# BLDC_wireless_project.net
KiCad netlist of a schematic drawn in EasyEDA Pro
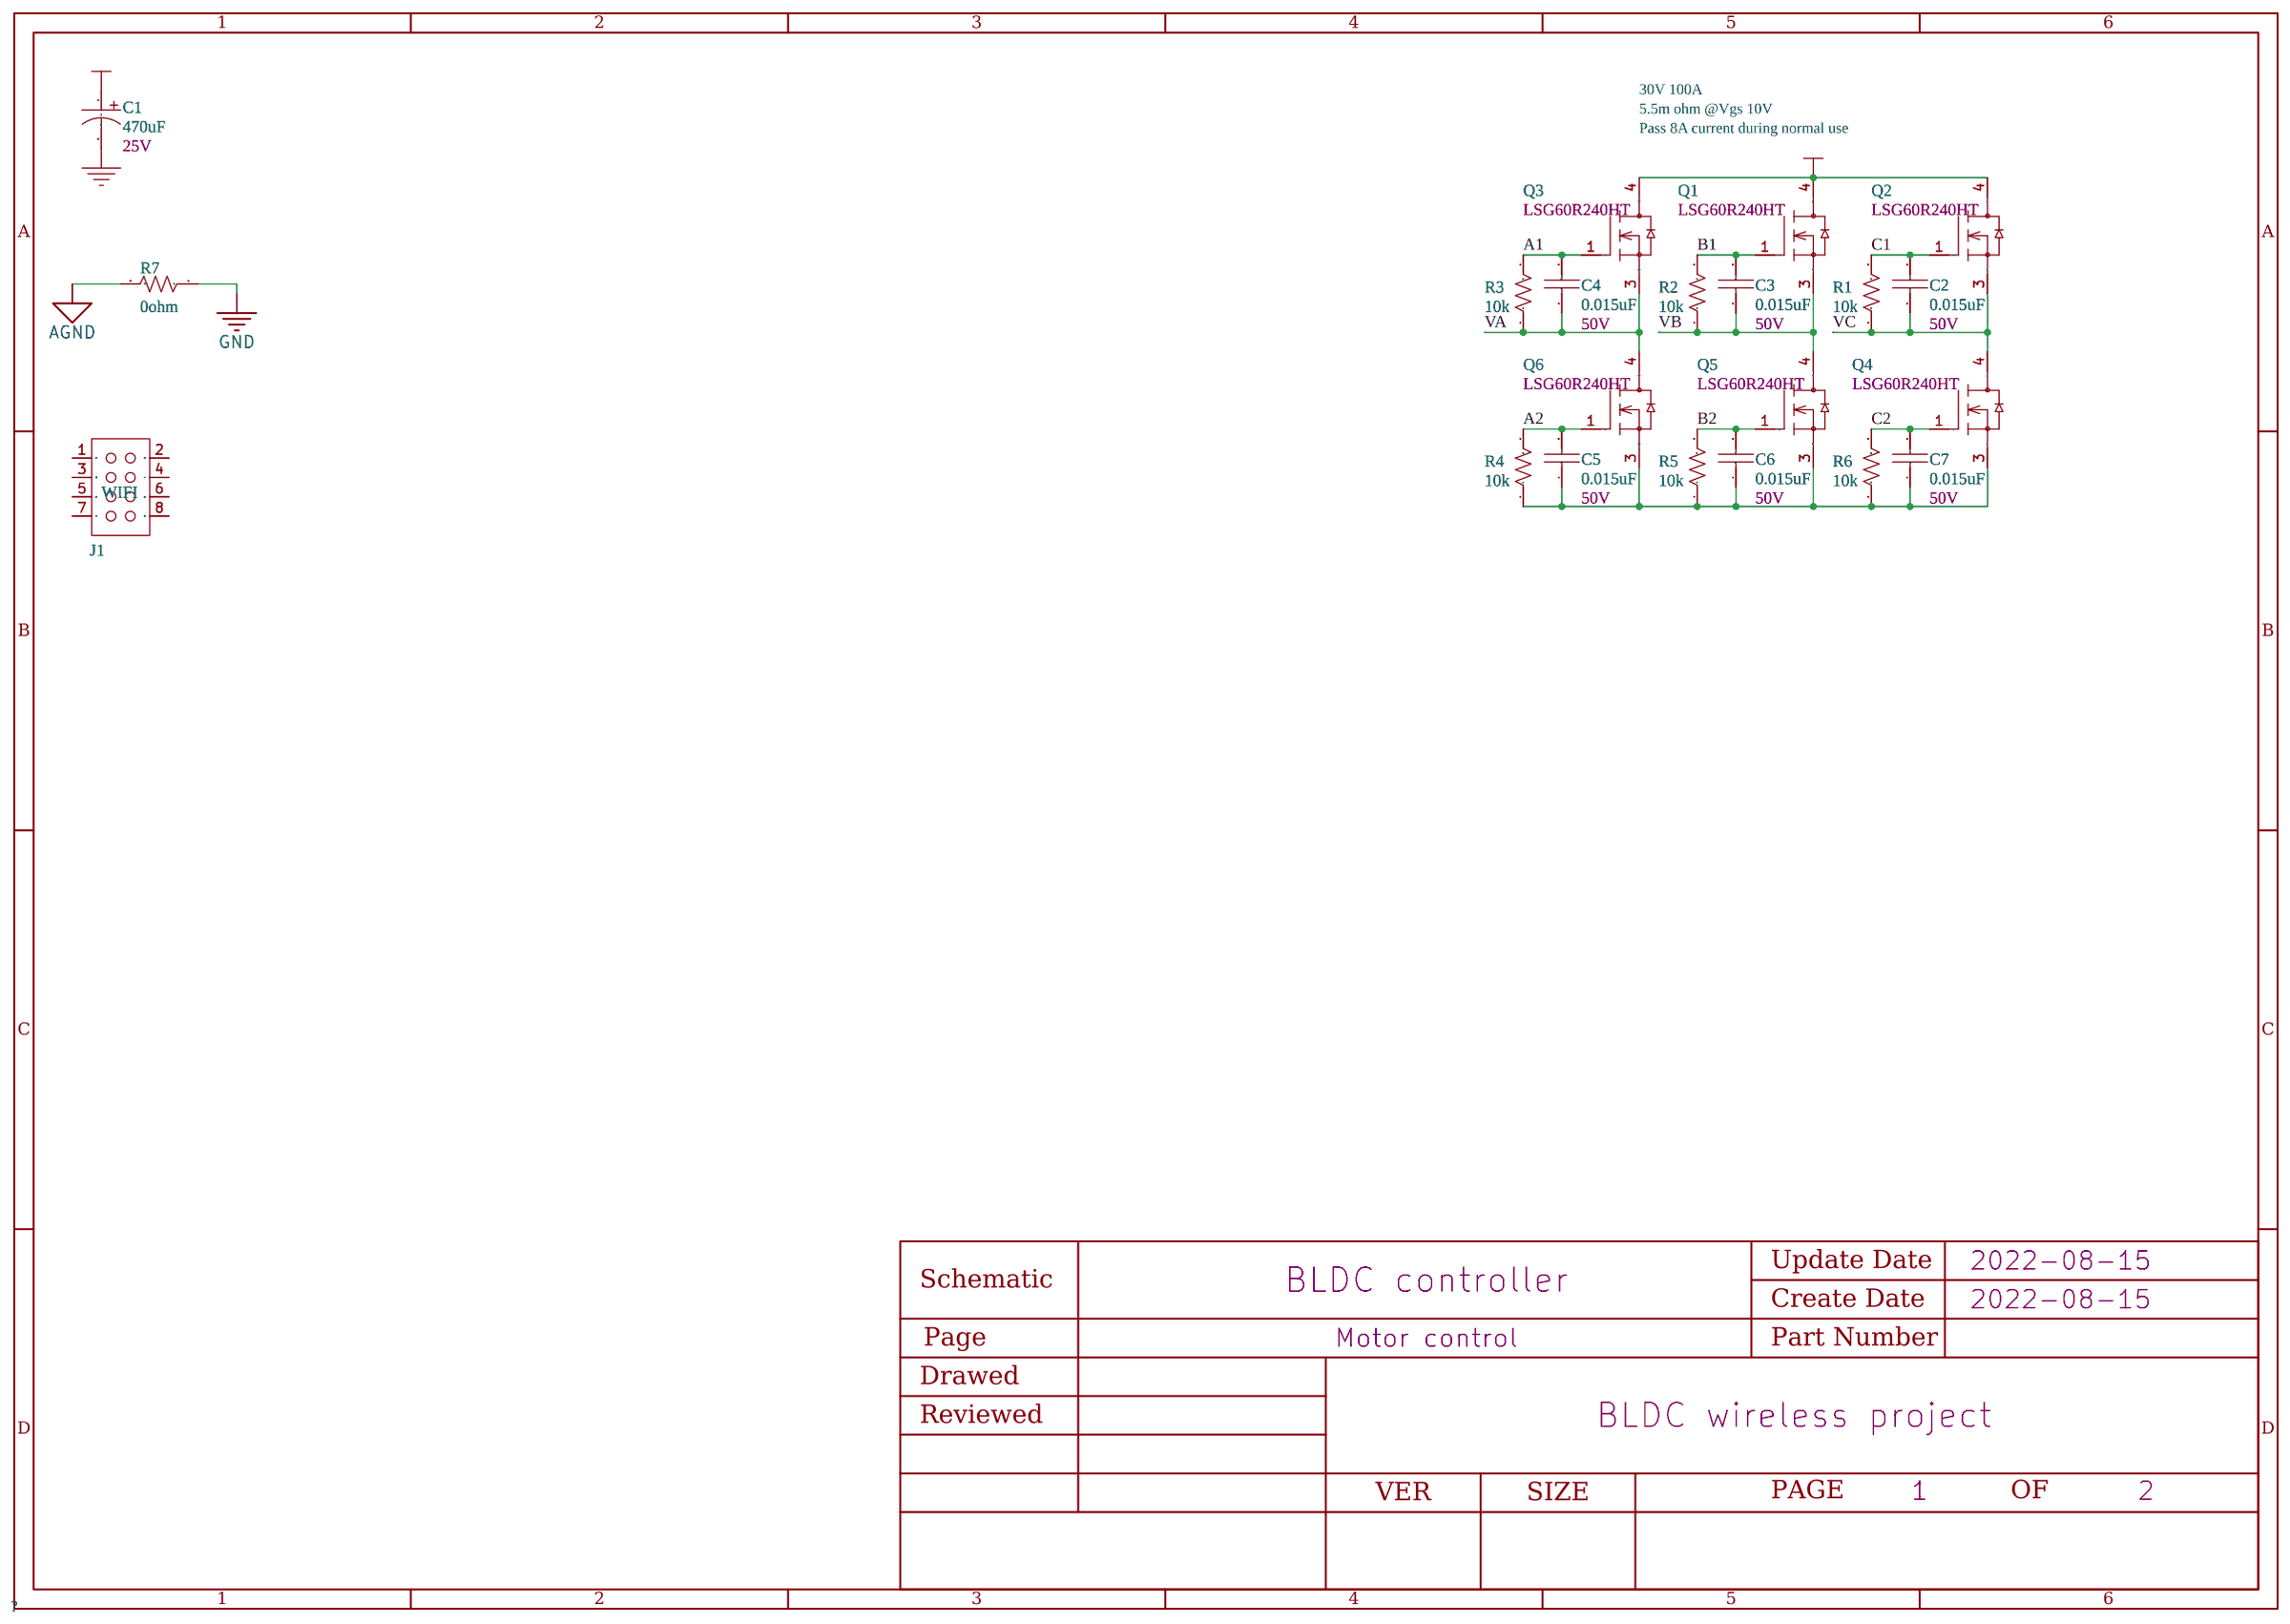
[diagram p0: Motor control]
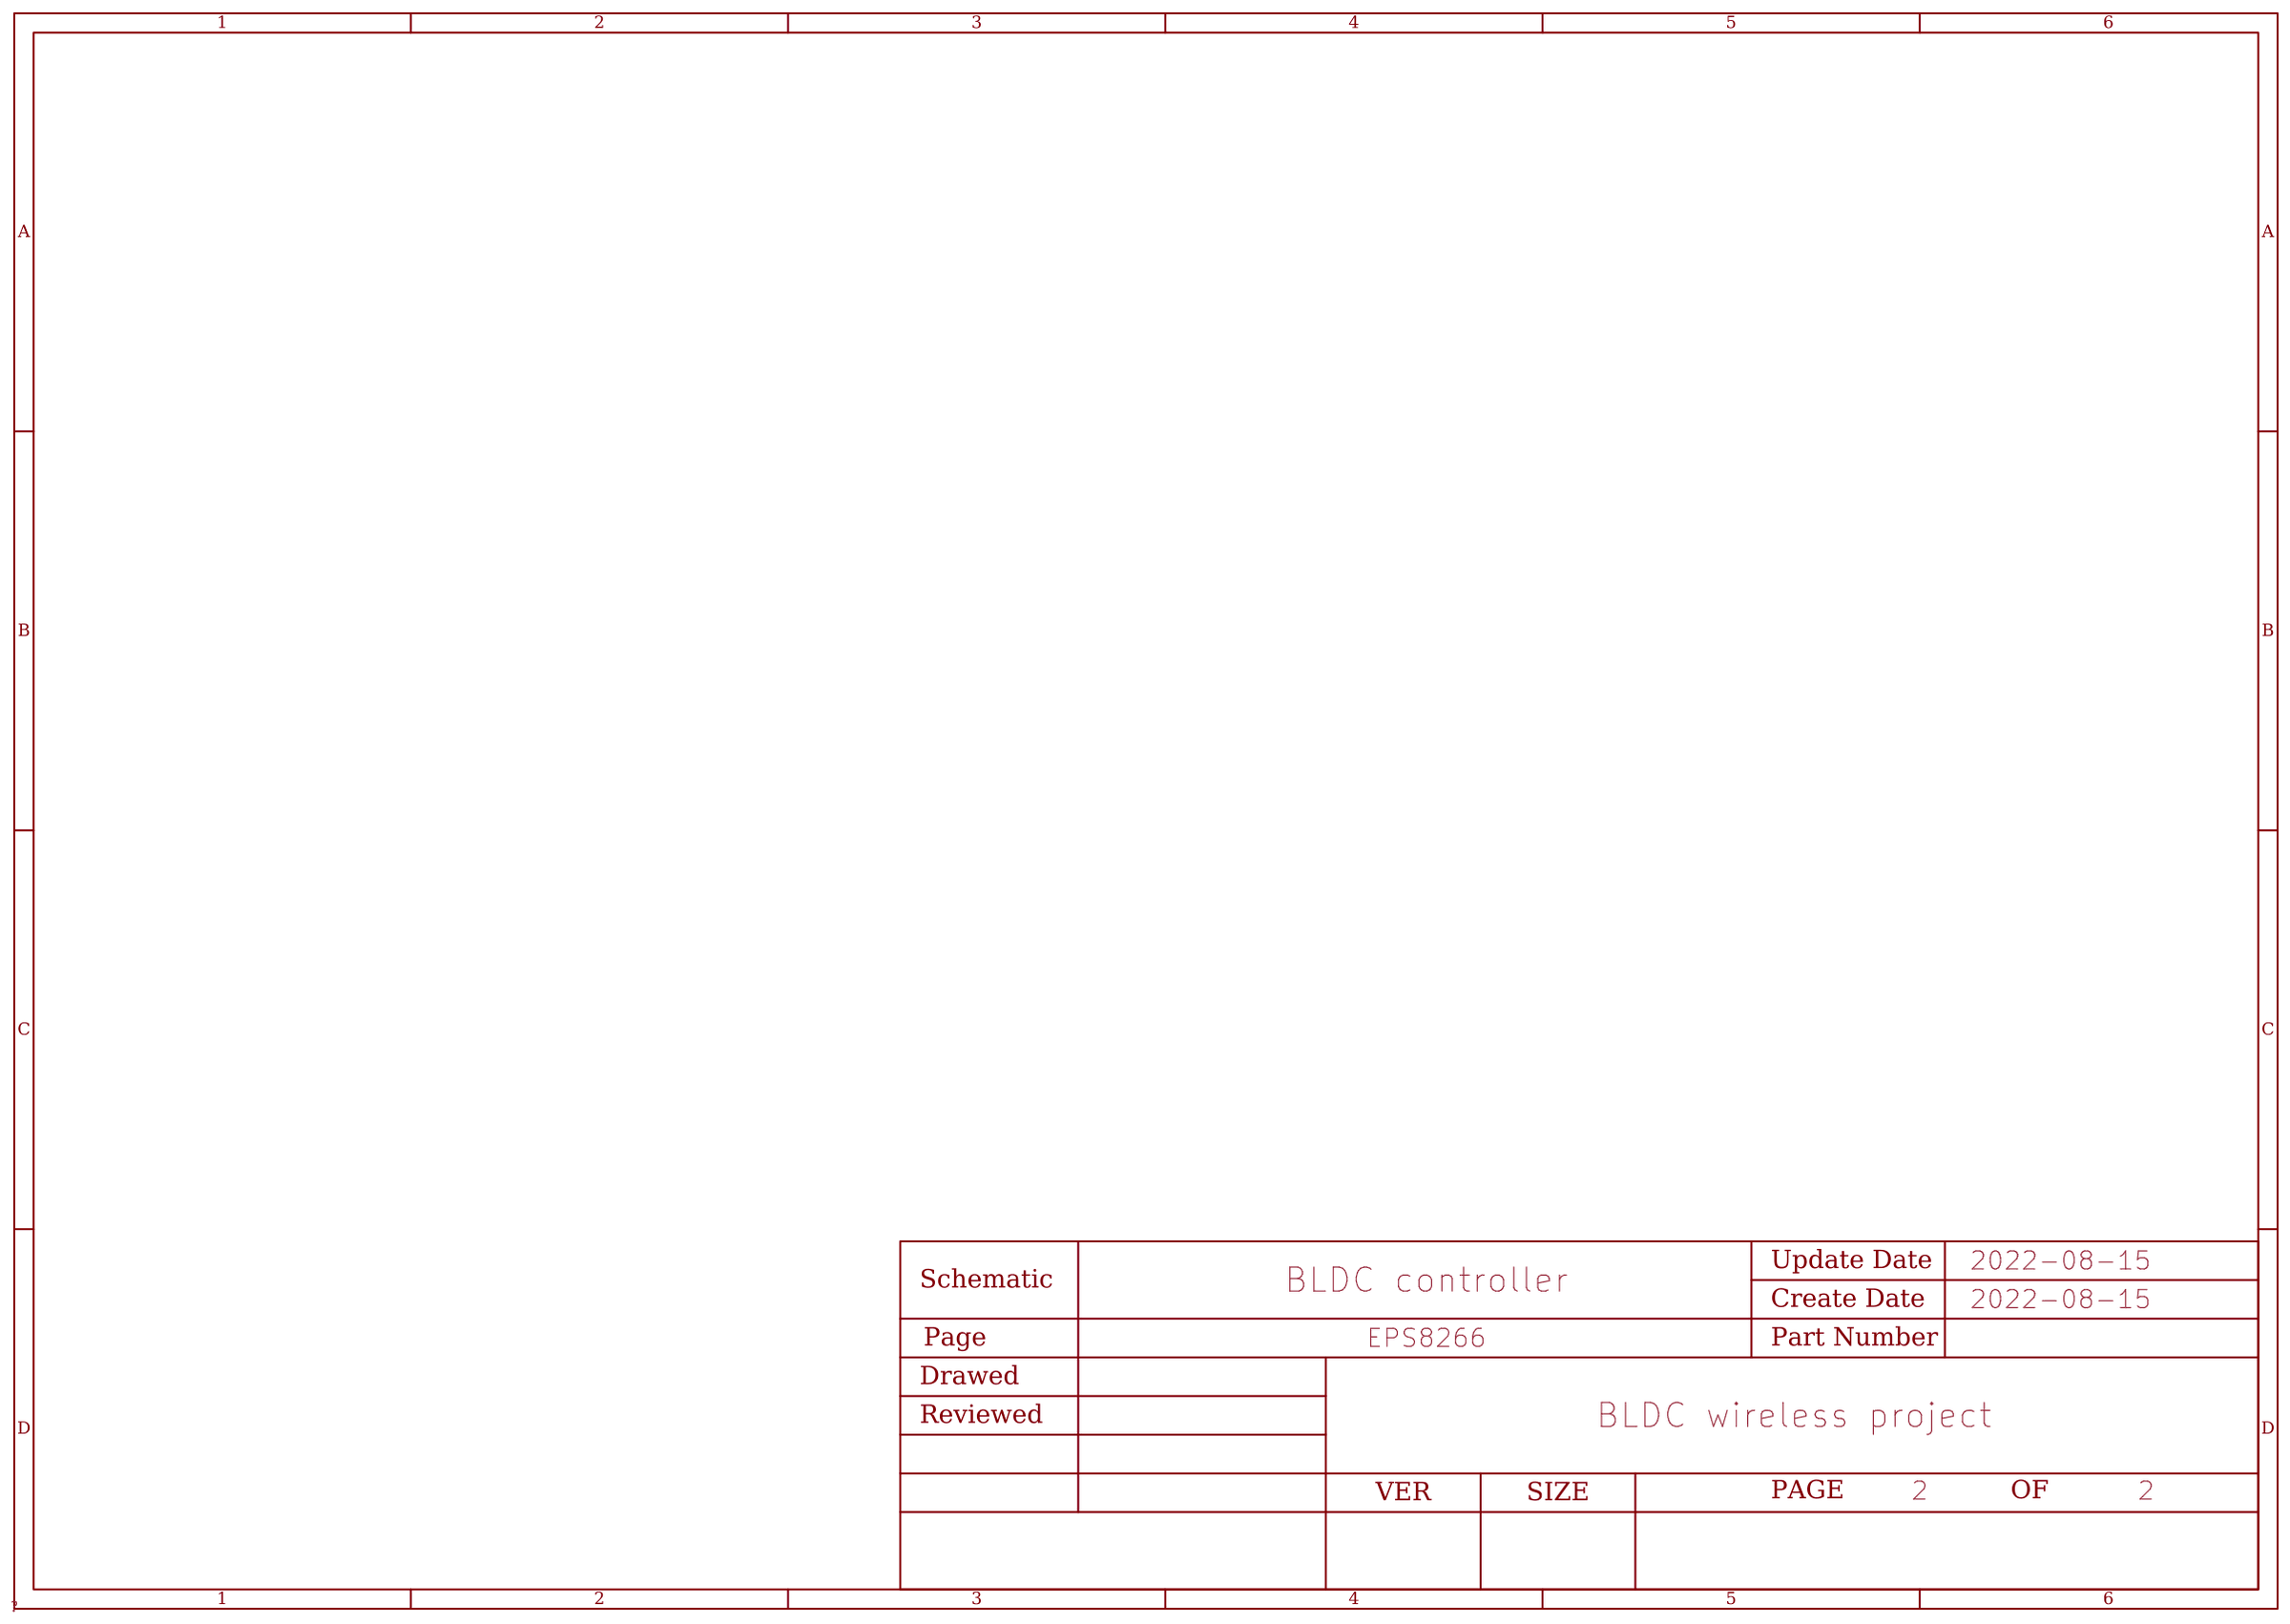
[diagram p1: EPS8266]

(export (version "E")
  (design (tool "Eeschema 10.0.6"))
  (components
    (comp (ref "C1")
      (value "470uF")
      (description "CHIP ELECT 470uF 25V 20% D10xL10 105")
      (fields (field (name "Tolerance") "20%") (field (name "Voltage") "25V"))
      (libsource (lib "easyedapro") (part "CAP E 470uF 25V 20% SMD"))
    )
    (comp (ref "C2")
      (value "0.015uF")
      (description "GP CHIP CAP 0.015uF 50V 10% 0603 TYPE X7R")
      (fields (field (name "Tolerance") "10%") (field (name "Voltage") "50V"))
      (libsource (lib "easyedapro") (part "CAP0603 0.015uF 50V 10%"))
    )
    (comp (ref "C3")
      (value "0.015uF")
      (description "GP CHIP CAP 0.015uF 50V 10% 0603 TYPE X7R")
      (fields (field (name "Tolerance") "10%") (field (name "Voltage") "50V"))
      (libsource (lib "easyedapro") (part "CAP0603 0.015uF 50V 10%"))
    )
    (comp (ref "C4")
      (value "0.015uF")
      (description "GP CHIP CAP 0.015uF 50V 10% 0603 TYPE X7R")
      (fields (field (name "Tolerance") "10%") (field (name "Voltage") "50V"))
      (libsource (lib "easyedapro") (part "CAP0603 0.015uF 50V 10%"))
    )
    (comp (ref "C5")
      (value "0.015uF")
      (description "GP CHIP CAP 0.015uF 50V 10% 0603 TYPE X7R")
      (fields (field (name "Tolerance") "10%") (field (name "Voltage") "50V"))
      (libsource (lib "easyedapro") (part "CAP0603 0.015uF 50V 10%"))
    )
    (comp (ref "C6")
      (value "0.015uF")
      (description "GP CHIP CAP 0.015uF 50V 10% 0603 TYPE X7R")
      (fields (field (name "Tolerance") "10%") (field (name "Voltage") "50V"))
      (libsource (lib "easyedapro") (part "CAP0603 0.015uF 50V 10%"))
    )
    (comp (ref "C7")
      (value "0.015uF")
      (description "GP CHIP CAP 0.015uF 50V 10% 0603 TYPE X7R")
      (fields (field (name "Tolerance") "10%") (field (name "Voltage") "50V"))
      (libsource (lib "easyedapro") (part "CAP0603 0.015uF 50V 10%"))
    )
    (comp (ref "J1")
      (value "2.54mm")
      (description "2X4P P:2.54MM 90掳 DIP K")
      (fields
        (field (name "MFG") "JINJIA")
        (field (name "MFG Part") "2.54-2X4AW-10.4")
        (field (name "CREATE_NAME") "Nathan")
      )
      (libsource (lib "easyedapro") (part "HEAD 8P 2X4 PH=2.54mm 90 H5mm_2.54-2X4AW-10.4"))
    )
    (comp (ref "Q1")
      (value "T5860038503A6")
      (description "NMOS 600V LSG60R240HT TO252( LONTEN K")
      (fields
        (field (name "MFG") "LONTEN")
        (field (name "MFG Part") "LSG60R240HT")
        (field (name "Voltage") "600V")
        (field (name "CREATE_NAME") "Nathan")
      )
      (libsource (lib "easyedapro") (part "NMOS LSG60R240HT"))
    )
    (comp (ref "Q2")
      (value "T5860038503A6")
      (description "NMOS 600V LSG60R240HT TO252( LONTEN K")
      (fields
        (field (name "MFG") "LONTEN")
        (field (name "MFG Part") "LSG60R240HT")
        (field (name "Voltage") "600V")
        (field (name "CREATE_NAME") "Nathan")
      )
      (libsource (lib "easyedapro") (part "NMOS LSG60R240HT"))
    )
    (comp (ref "Q3")
      (value "T5860038503A6")
      (description "NMOS 600V LSG60R240HT TO252( LONTEN K")
      (fields
        (field (name "MFG") "LONTEN")
        (field (name "MFG Part") "LSG60R240HT")
        (field (name "Voltage") "600V")
        (field (name "CREATE_NAME") "Nathan")
      )
      (libsource (lib "easyedapro") (part "NMOS LSG60R240HT"))
    )
    (comp (ref "Q4")
      (value "T5860038503A6")
      (description "NMOS 600V LSG60R240HT TO252( LONTEN K")
      (fields
        (field (name "MFG") "LONTEN")
        (field (name "MFG Part") "LSG60R240HT")
        (field (name "Voltage") "600V")
        (field (name "CREATE_NAME") "Nathan")
      )
      (libsource (lib "easyedapro") (part "NMOS LSG60R240HT"))
    )
    (comp (ref "Q5")
      (value "T5860038503A6")
      (description "NMOS 600V LSG60R240HT TO252( LONTEN K")
      (fields
        (field (name "MFG") "LONTEN")
        (field (name "MFG Part") "LSG60R240HT")
        (field (name "Voltage") "600V")
        (field (name "CREATE_NAME") "Nathan")
      )
      (libsource (lib "easyedapro") (part "NMOS LSG60R240HT"))
    )
    (comp (ref "Q6")
      (value "T5860038503A6")
      (description "NMOS 600V LSG60R240HT TO252( LONTEN K")
      (fields
        (field (name "MFG") "LONTEN")
        (field (name "MFG Part") "LSG60R240HT")
        (field (name "Voltage") "600V")
        (field (name "CREATE_NAME") "Nathan")
      )
      (libsource (lib "easyedapro") (part "NMOS LSG60R240HT"))
    )
    (comp (ref "R1")
      (value "10k")
      (description "CHIP 4.42K OHM 200PPM +-1% 0201 WALS L")
      (fields
        (field (name "MFG") "WALSIN (鑿柊)")
        (field (name "MFG Part") "WR02X4421FAL")
        (field (name "CREATE_NAME") "Nathan")
      )
      (libsource (lib "easyedapro") (part "RES0201 1/20W 1% 4.42K OHM_WALSIN"))
    )
    (comp (ref "R2")
      (value "10k")
      (description "CHIP 4.42K OHM 200PPM +-1% 0201 WALS L")
      (fields
        (field (name "MFG") "WALSIN (鑿柊)")
        (field (name "MFG Part") "WR02X4421FAL")
        (field (name "CREATE_NAME") "Nathan")
      )
      (libsource (lib "easyedapro") (part "RES0201 1/20W 1% 4.42K OHM_WALSIN"))
    )
    (comp (ref "R3")
      (value "10k")
      (description "CHIP 4.42K OHM 200PPM +-1% 0201 WALS L")
      (fields
        (field (name "MFG") "WALSIN (鑿柊)")
        (field (name "MFG Part") "WR02X4421FAL")
        (field (name "CREATE_NAME") "Nathan")
      )
      (libsource (lib "easyedapro") (part "RES0201 1/20W 1% 4.42K OHM_WALSIN"))
    )
    (comp (ref "R4")
      (value "10k")
      (description "CHIP 4.42K OHM 200PPM +-1% 0201 WALS L")
      (fields
        (field (name "MFG") "WALSIN (鑿柊)")
        (field (name "MFG Part") "WR02X4421FAL")
        (field (name "CREATE_NAME") "Nathan")
      )
      (libsource (lib "easyedapro") (part "RES0201 1/20W 1% 4.42K OHM_WALSIN"))
    )
    (comp (ref "R5")
      (value "10k")
      (description "CHIP 4.42K OHM 200PPM +-1% 0201 WALS L")
      (fields
        (field (name "MFG") "WALSIN (鑿柊)")
        (field (name "MFG Part") "WR02X4421FAL")
        (field (name "CREATE_NAME") "Nathan")
      )
      (libsource (lib "easyedapro") (part "RES0201 1/20W 1% 4.42K OHM_WALSIN"))
    )
    (comp (ref "R6")
      (value "10k")
      (description "CHIP 4.42K OHM 200PPM +-1% 0201 WALS L")
      (fields
        (field (name "MFG") "WALSIN (鑿柊)")
        (field (name "MFG Part") "WR02X4421FAL")
        (field (name "CREATE_NAME") "Nathan")
      )
      (libsource (lib "easyedapro") (part "RES0201 1/20W 1% 4.42K OHM_WALSIN"))
    )
    (comp (ref "R7")
      (value "0ohm")
      (description "CHIP 4.42K OHM 200PPM +-1% 0201 WALS L")
      (fields
        (field (name "MFG") "WALSIN (鑿柊)")
        (field (name "MFG Part") "WR02X4421FAL")
        (field (name "CREATE_NAME") "Nathan")
      )
      (libsource (lib "easyedapro") (part "RES0201 1/20W 1% 4.42K OHM_WALSIN"))
    )
  )
  (nets
    (net (code "1") (name "A1") (class "Default")
      (node (ref "C4") (pin "2") (pinfunction "2_2") (pintype "input"))
      (node (ref "Q3") (pin "1") (pinfunction "G_1") (pintype "input"))
      (node (ref "R3") (pin "2") (pinfunction "2_2") (pintype "input"))
    )
    (net (code "2") (name "A2") (class "Default")
      (node (ref "C5") (pin "2") (pinfunction "2_2") (pintype "input"))
      (node (ref "Q6") (pin "1") (pinfunction "G_1") (pintype "input"))
      (node (ref "R4") (pin "2") (pinfunction "2_2") (pintype "input"))
    )
    (net (code "3") (name "AGND") (class "Default")
      (node (ref "R7") (pin "2") (pinfunction "2_2") (pintype "input"))
    )
    (net (code "4") (name "B1") (class "Default")
      (node (ref "C3") (pin "2") (pinfunction "2_2") (pintype "input"))
      (node (ref "Q1") (pin "1") (pinfunction "G_1") (pintype "input"))
      (node (ref "R2") (pin "2") (pinfunction "2_2") (pintype "input"))
    )
    (net (code "5") (name "B2") (class "Default")
      (node (ref "C6") (pin "2") (pinfunction "2_2") (pintype "input"))
      (node (ref "Q5") (pin "1") (pinfunction "G_1") (pintype "input"))
      (node (ref "R5") (pin "2") (pinfunction "2_2") (pintype "input"))
    )
    (net (code "6") (name "C1") (class "Default")
      (node (ref "C2") (pin "2") (pinfunction "2_2") (pintype "input"))
      (node (ref "Q2") (pin "1") (pinfunction "G_1") (pintype "input"))
      (node (ref "R1") (pin "2") (pinfunction "2_2") (pintype "input"))
    )
    (net (code "7") (name "C2") (class "Default")
      (node (ref "C7") (pin "2") (pinfunction "2_2") (pintype "input"))
      (node (ref "Q4") (pin "1") (pinfunction "G_1") (pintype "input"))
      (node (ref "R6") (pin "2") (pinfunction "2_2") (pintype "input"))
    )
    (net (code "8") (name "GND") (class "Default")
      (node (ref "C1") (pin "2") (pinfunction "2_2") (pintype "input"))
      (node (ref "R7") (pin "1") (pinfunction "1_1") (pintype "input"))
    )
    (net (code "9") (name "Net-(Q4-S)") (class "Default")
      (node (ref "C5") (pin "1") (pinfunction "1_1") (pintype "input"))
      (node (ref "C6") (pin "1") (pinfunction "1_1") (pintype "input"))
      (node (ref "C7") (pin "1") (pinfunction "1_1") (pintype "input"))
      (node (ref "Q4") (pin "3") (pinfunction "S_3") (pintype "input"))
      (node (ref "Q5") (pin "3") (pinfunction "S_3") (pintype "input"))
      (node (ref "Q6") (pin "3") (pinfunction "S_3") (pintype "input"))
      (node (ref "R4") (pin "1") (pinfunction "1_1") (pintype "input"))
      (node (ref "R5") (pin "1") (pinfunction "1_1") (pintype "input"))
      (node (ref "R6") (pin "1") (pinfunction "1_1") (pintype "input"))
    )
    (net (code "10") (name "VA") (class "Default")
      (node (ref "C4") (pin "1") (pinfunction "1_1") (pintype "input"))
      (node (ref "Q3") (pin "3") (pinfunction "S_3") (pintype "input"))
      (node (ref "Q6") (pin "4") (pinfunction "D_4") (pintype "input"))
      (node (ref "R3") (pin "1") (pinfunction "1_1") (pintype "input"))
    )
    (net (code "11") (name "VB") (class "Default")
      (node (ref "C3") (pin "1") (pinfunction "1_1") (pintype "input"))
      (node (ref "Q1") (pin "3") (pinfunction "S_3") (pintype "input"))
      (node (ref "Q5") (pin "4") (pinfunction "D_4") (pintype "input"))
      (node (ref "R2") (pin "1") (pinfunction "1_1") (pintype "input"))
    )
    (net (code "12") (name "VC") (class "Default")
      (node (ref "C2") (pin "1") (pinfunction "1_1") (pintype "input"))
      (node (ref "Q2") (pin "3") (pinfunction "S_3") (pintype "input"))
      (node (ref "Q4") (pin "4") (pinfunction "D_4") (pintype "input"))
      (node (ref "R1") (pin "1") (pinfunction "1_1") (pintype "input"))
    )
    (net (code "13") (name "V_BAT") (class "Default")
      (node (ref "C1") (pin "1") (pinfunction "1_1") (pintype "input"))
      (node (ref "Q1") (pin "4") (pinfunction "D_4") (pintype "input"))
      (node (ref "Q2") (pin "4") (pinfunction "D_4") (pintype "input"))
      (node (ref "Q3") (pin "4") (pinfunction "D_4") (pintype "input"))
    )
    (net (code "14") (name "unconnected-(J1-Pad1)") (class "Default")
      (node (ref "J1") (pin "1") (pinfunction "1_1") (pintype "input"))
    )
    (net (code "15") (name "unconnected-(J1-Pad2)") (class "Default")
      (node (ref "J1") (pin "2") (pinfunction "2_2") (pintype "input"))
    )
    (net (code "16") (name "unconnected-(J1-Pad3)") (class "Default")
      (node (ref "J1") (pin "3") (pinfunction "3_3") (pintype "input"))
    )
    (net (code "17") (name "unconnected-(J1-Pad4)") (class "Default")
      (node (ref "J1") (pin "4") (pinfunction "4_4") (pintype "input"))
    )
    (net (code "18") (name "unconnected-(J1-Pad5)") (class "Default")
      (node (ref "J1") (pin "5") (pinfunction "5_5") (pintype "input"))
    )
    (net (code "19") (name "unconnected-(J1-Pad6)") (class "Default")
      (node (ref "J1") (pin "6") (pinfunction "6_6") (pintype "input"))
    )
    (net (code "20") (name "unconnected-(J1-Pad7)") (class "Default")
      (node (ref "J1") (pin "7") (pinfunction "7_7") (pintype "input"))
    )
    (net (code "21") (name "unconnected-(J1-Pad8)") (class "Default")
      (node (ref "J1") (pin "8") (pinfunction "8_8") (pintype "input"))
    )
  )
)
